# Testplatine_01_wiebeauftragt.net
KiCad netlist of a schematic drawn in EAGLE
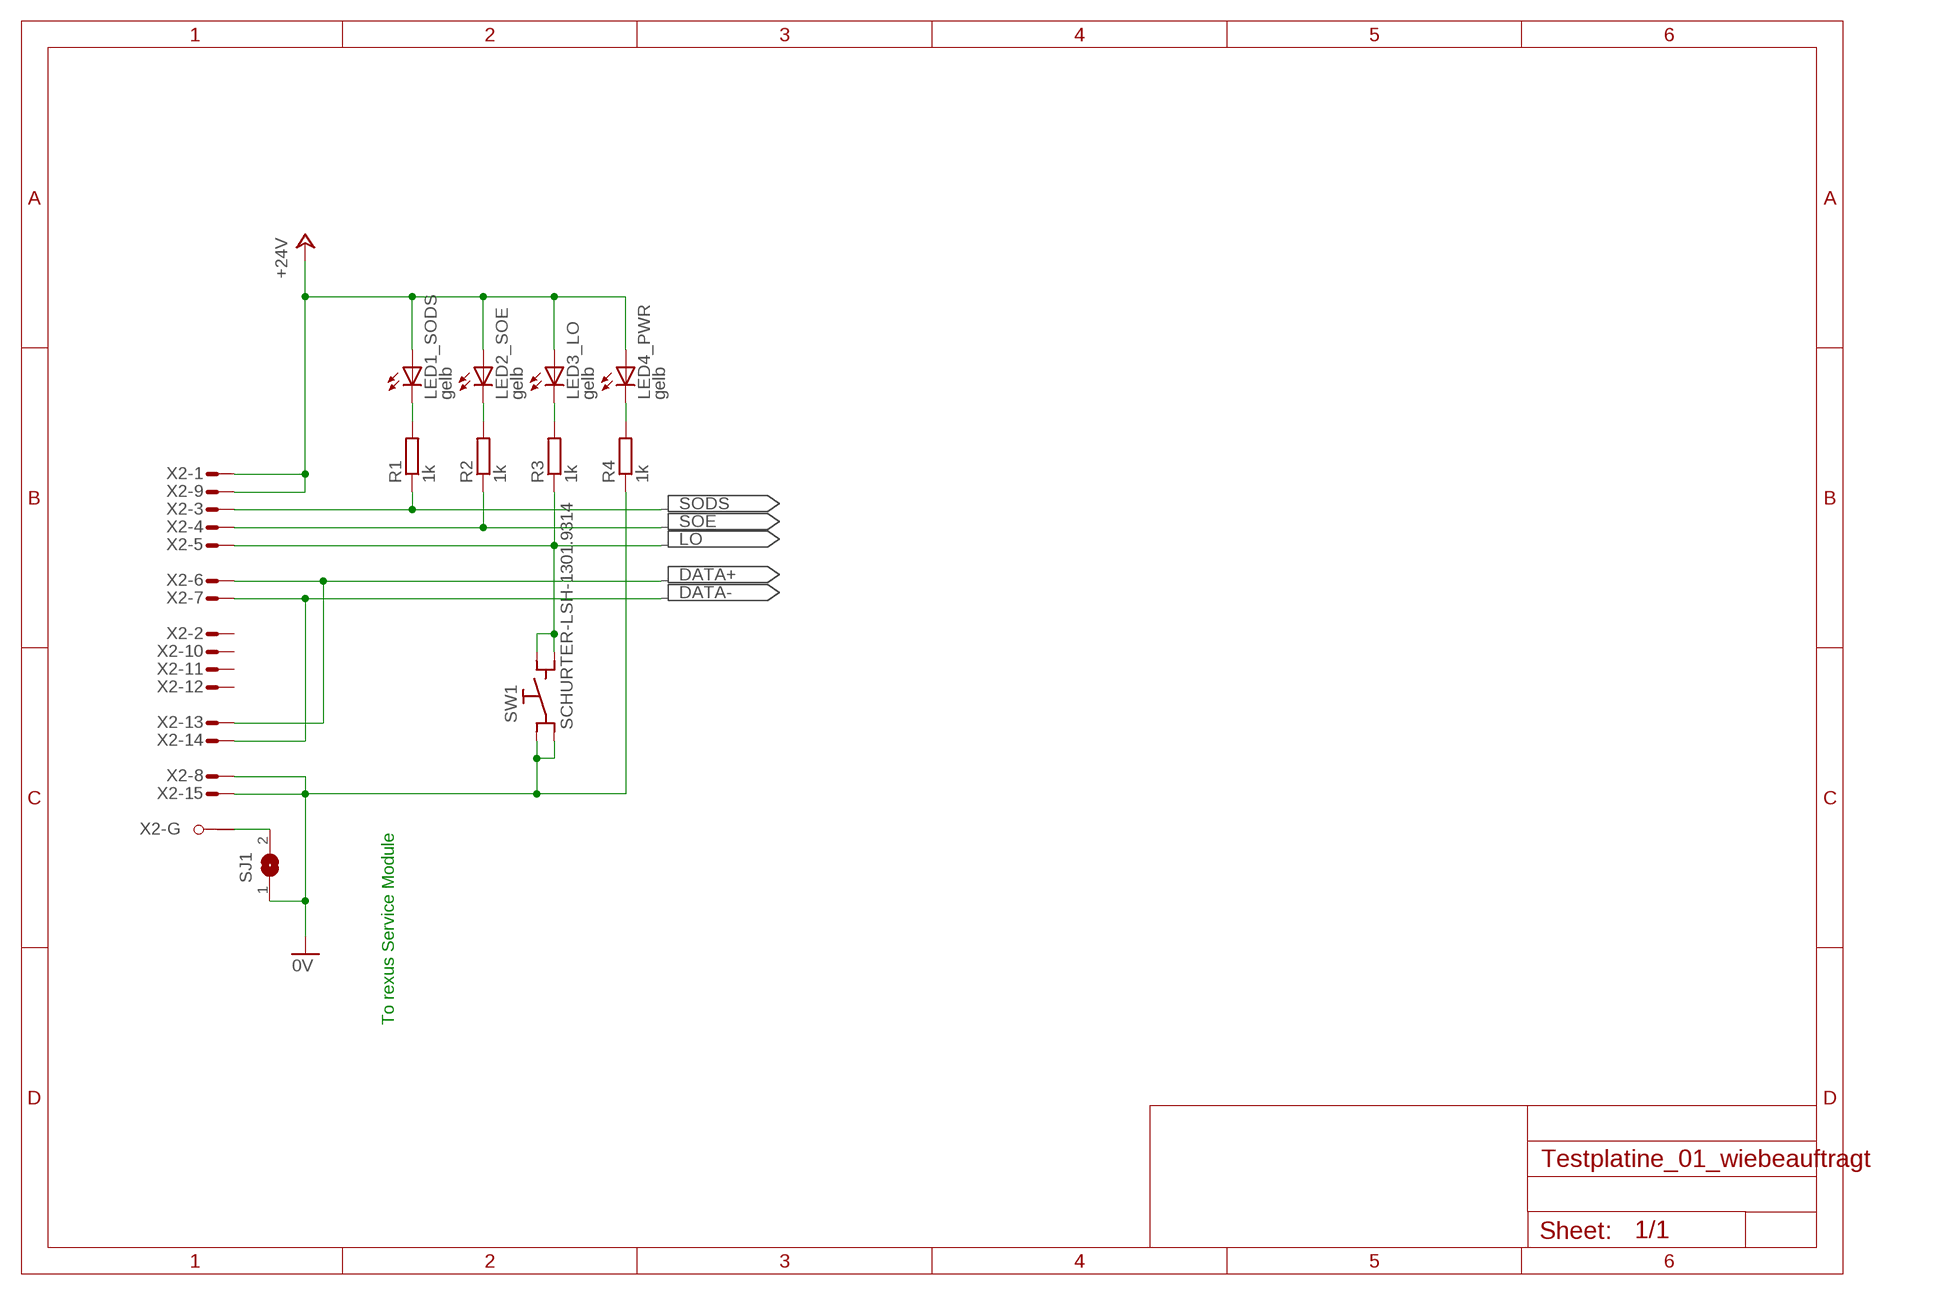
[diagram p0: schematic, sheet 1]

(export (version "E")
  (design (tool "Eeschema 10.0.6"))
  (components
    (comp (ref "LED1_SODS")
      (value "gelb")
      (footprint "eagle-import:CHIPLED_0805")
      (libsource (lib "eagle-import") (part "LEDCHIPLED_0805"))
    )
    (comp (ref "LED2_SOE")
      (value "gelb")
      (footprint "eagle-import:CHIPLED_0805")
      (libsource (lib "eagle-import") (part "LEDCHIPLED_0805"))
    )
    (comp (ref "LED3_LO")
      (value "gelb")
      (footprint "eagle-import:CHIPLED_0805")
      (libsource (lib "eagle-import") (part "LEDCHIPLED_0805"))
    )
    (comp (ref "LED4_PWR")
      (value "gelb")
      (footprint "eagle-import:CHIPLED_0805")
      (libsource (lib "eagle-import") (part "LEDCHIPLED_0805"))
    )
    (comp (ref "R1")
      (value "1k")
      (footprint "eagle-import:R0805")
      (libsource (lib "eagle-import") (part "R-EU_R0805"))
    )
    (comp (ref "R2")
      (value "1k")
      (footprint "eagle-import:R0805")
      (libsource (lib "eagle-import") (part "R-EU_R0805"))
    )
    (comp (ref "R3")
      (value "1k")
      (footprint "eagle-import:R0805")
      (libsource (lib "eagle-import") (part "R-EU_R0805"))
    )
    (comp (ref "R4")
      (value "1k")
      (footprint "eagle-import:R0805")
      (libsource (lib "eagle-import") (part "R-EU_R0805"))
    )
    (comp (ref "SJ1") (value "SJ") (footprint "eagle-import:SJ") (libsource (lib "eagle-import") (part "SJ")))
    (comp (ref "SW1")
      (value "SCHURTER-LSH-1301.9314")
      (footprint "eagle-import:LSH")
      (libsource (lib "eagle-import") (part "SCHURTER-LSH-1301.9314"))
    )
    (comp (ref "X2")
      (value "M15HPS")
      (footprint "eagle-import:M15HP")
      (fields
        (field (name "OC_FARNELL") "1097065 + 2x 1855027")
        (field (name "OC_RS") "692-7976 + 2x 719-9753")
      )
      (libsource (lib "eagle-import") (part "M15HPS"))
    )
  )
  (nets
    (net (code "1") (name "+24V") (class "Default")
      (node (ref "LED1_SODS") (pin "A") (pinfunction "A_A") (pintype "passive"))
      (node (ref "LED2_SOE") (pin "A") (pinfunction "A_A") (pintype "passive"))
      (node (ref "LED3_LO") (pin "A") (pinfunction "A_A") (pintype "passive"))
      (node (ref "LED4_PWR") (pin "A") (pinfunction "A_A") (pintype "passive"))
      (node (ref "X2") (pin "1") (pinfunction "M_1") (pintype "passive"))
      (node (ref "X2") (pin "9") (pinfunction "M_9") (pintype "passive"))
    )
    (net (code "2") (name "/DATA+") (class "Default")
      (node (ref "X2") (pin "13") (pinfunction "M_13") (pintype "passive"))
      (node (ref "X2") (pin "6") (pinfunction "M_6") (pintype "passive"))
    )
    (net (code "3") (name "/DATA-") (class "Default")
      (node (ref "X2") (pin "14") (pinfunction "M_14") (pintype "passive"))
      (node (ref "X2") (pin "7") (pinfunction "M_7") (pintype "passive"))
    )
    (net (code "4") (name "/LO") (class "Default")
      (node (ref "R3") (pin "1") (pinfunction "1_1") (pintype "passive"))
      (node (ref "SW1") (pin "NO1") (pinfunction "NO_NO1") (pintype "passive"))
      (node (ref "SW1") (pin "NO2") (pinfunction "NO_NO2") (pintype "passive"))
      (node (ref "X2") (pin "5") (pinfunction "M_5") (pintype "passive"))
    )
    (net (code "5") (name "/SODS") (class "Default")
      (node (ref "R1") (pin "1") (pinfunction "1_1") (pintype "passive"))
      (node (ref "X2") (pin "3") (pinfunction "M_3") (pintype "passive"))
    )
    (net (code "6") (name "/SOE") (class "Default")
      (node (ref "R2") (pin "1") (pinfunction "1_1") (pintype "passive"))
      (node (ref "X2") (pin "4") (pinfunction "M_4") (pintype "passive"))
    )
    (net (code "7") (name "0V") (class "Default")
      (node (ref "R4") (pin "1") (pinfunction "1_1") (pintype "passive"))
      (node (ref "SJ1") (pin "1") (pinfunction "1_1") (pintype "passive"))
      (node (ref "SW1") (pin "C1") (pinfunction "C_C1") (pintype "passive"))
      (node (ref "SW1") (pin "C2") (pinfunction "C_C2") (pintype "passive"))
      (node (ref "X2") (pin "15") (pinfunction "M_15") (pintype "passive"))
      (node (ref "X2") (pin "8") (pinfunction "M_8") (pintype "passive"))
    )
    (net (code "8") (name "Net-(LED1_SODS-PadC)") (class "Default")
      (node (ref "LED1_SODS") (pin "C") (pinfunction "C_C") (pintype "passive"))
      (node (ref "R1") (pin "2") (pinfunction "2_2") (pintype "passive"))
    )
    (net (code "9") (name "Net-(LED2_SOE-PadC)") (class "Default")
      (node (ref "LED2_SOE") (pin "C") (pinfunction "C_C") (pintype "passive"))
      (node (ref "R2") (pin "2") (pinfunction "2_2") (pintype "passive"))
    )
    (net (code "10") (name "Net-(LED3_LO-PadC)") (class "Default")
      (node (ref "LED3_LO") (pin "C") (pinfunction "C_C") (pintype "passive"))
      (node (ref "R3") (pin "2") (pinfunction "2_2") (pintype "passive"))
    )
    (net (code "11") (name "Net-(LED4_PWR-PadC)") (class "Default")
      (node (ref "LED4_PWR") (pin "C") (pinfunction "C_C") (pintype "passive"))
      (node (ref "R4") (pin "2") (pinfunction "2_2") (pintype "passive"))
    )
    (net (code "12") (name "Net-(SJ1-Pad2)") (class "Default")
      (node (ref "SJ1") (pin "2") (pinfunction "2_2") (pintype "passive"))
      (node (ref "X2") (pin "G1") (pinfunction "G1_G1") (pintype "passive"))
    )
    (net (code "13") (name "unconnected-(X2-PadG2)") (class "Default")
      (node (ref "X2") (pin "G2") (pinfunction "G2_G2") (pintype "passive"))
    )
    (net (code "14") (name "unconnected-(X2B-M-Pad10)") (class "Default")
      (node (ref "X2") (pin "10") (pinfunction "M_10") (pintype "passive"))
    )
    (net (code "15") (name "unconnected-(X2C-M-Pad11)") (class "Default")
      (node (ref "X2") (pin "11") (pinfunction "M_11") (pintype "passive"))
    )
    (net (code "16") (name "unconnected-(X2D-M-Pad12)") (class "Default")
      (node (ref "X2") (pin "12") (pinfunction "M_12") (pintype "passive"))
    )
    (net (code "17") (name "unconnected-(X2H-M-Pad2)") (class "Default")
      (node (ref "X2") (pin "2") (pinfunction "M_2") (pintype "passive"))
    )
  )
)
